# smarty01.net
KiCad netlist of a schematic drawn in EAGLE
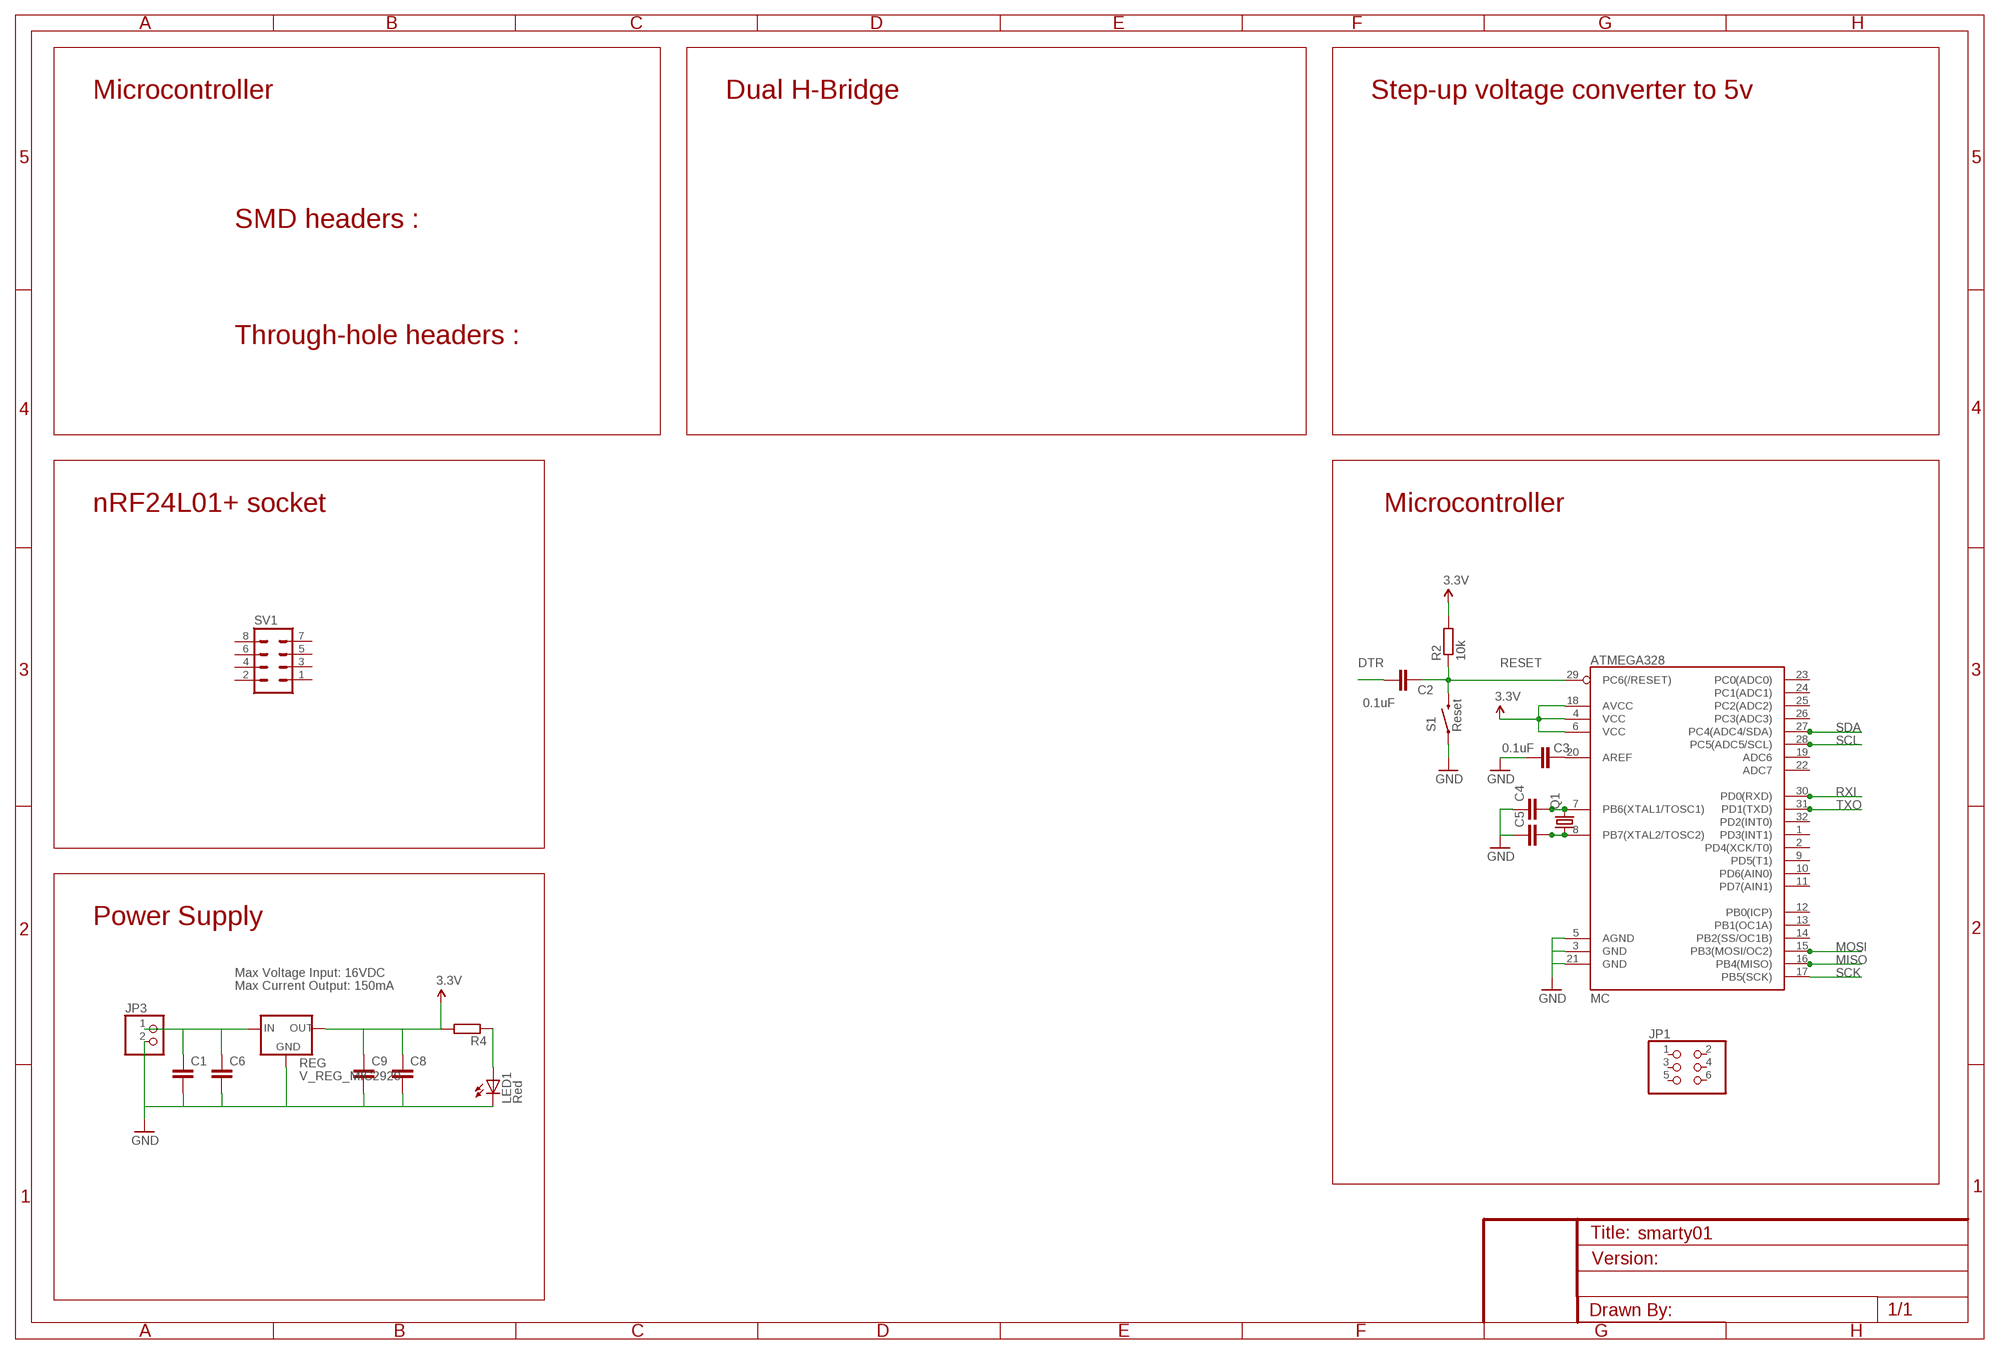
[diagram p0: schematic, sheet 1]

(export (version "E")
  (design (tool "Eeschema 10.0.6"))
  (components
    (comp (ref "C1")
      (value "C-EUC0805")
      (footprint "eagle-import:C0805")
      (libsource (lib "eagle-import") (part "C-EUC0805"))
    )
    (comp (ref "C2")
      (value "0.1uF")
      (footprint "eagle-import:C0805")
      (libsource (lib "eagle-import") (part "C-EUC0805"))
    )
    (comp (ref "C3")
      (value "0.1uF")
      (footprint "eagle-import:C0805")
      (libsource (lib "eagle-import") (part "C-EUC0805"))
    )
    (comp (ref "C4")
      (value "C-EUC0805")
      (footprint "eagle-import:C0805")
      (libsource (lib "eagle-import") (part "C-EUC0805"))
    )
    (comp (ref "C5")
      (value "C-EUC0805")
      (footprint "eagle-import:C0805")
      (libsource (lib "eagle-import") (part "C-EUC0805"))
    )
    (comp (ref "C6")
      (value "C-EUC0805")
      (footprint "eagle-import:C0805")
      (libsource (lib "eagle-import") (part "C-EUC0805"))
    )
    (comp (ref "C8")
      (value "C-EUC0805")
      (footprint "eagle-import:C0805")
      (libsource (lib "eagle-import") (part "C-EUC0805"))
    )
    (comp (ref "C9")
      (value "C-EUC0805")
      (footprint "eagle-import:C0805")
      (libsource (lib "eagle-import") (part "C-EUC0805"))
    )
    (comp (ref "JP1")
      (value "PINHD-2X03_2.54-SMD")
      (footprint "eagle-import:2X03SMD")
      (libsource (lib "eagle-import") (part "PINHD-2X03_2.54-SMD"))
    )
    (comp (ref "JP3")
      (value "PINHD-1X2")
      (footprint "eagle-import:1X02")
      (libsource (lib "eagle-import") (part "PINHD-1X2"))
    )
    (comp (ref "LED1")
      (value "Red")
      (footprint "eagle-import:LED-0603")
      (libsource (lib "eagle-import") (part "LED0603"))
    )
    (comp (ref "MC")
      (value "ATMEGA328")
      (footprint "eagle-import:TQFP32-08")
      (libsource (lib "eagle-import") (part "ATMEGA168"))
    )
    (comp (ref "Q1")
      (value "CRYSTALHC49UP")
      (footprint "eagle-import:HC49UP")
      (libsource (lib "eagle-import") (part "CRYSTALHC49UP"))
    )
    (comp (ref "R2")
      (value "10k")
      (footprint "eagle-import:R0805")
      (libsource (lib "eagle-import") (part "R-EU_R0805"))
    )
    (comp (ref "R4")
      (value "R-EU_R0805")
      (footprint "eagle-import:R0805")
      (libsource (lib "eagle-import") (part "R-EU_R0805"))
    )
    (comp (ref "REG")
      (value "V_REG_MIC2920")
      (footprint "eagle-import:SOT223")
      (libsource (lib "eagle-import") (part "V_REG_MIC2920"))
    )
    (comp (ref "S1")
      (value "Reset")
      (footprint "eagle-import:TACTILE_SWITCH_SMD")
      (libsource (lib "eagle-import") (part "SWITCH-MOMENTARY-2SMD"))
    )
    (comp (ref "SV1")
      (value "MA04-2")
      (footprint "eagle-import:MA04-2")
      (libsource (lib "eagle-import") (part "MA04-2"))
    )
  )
  (nets
    (net (code "1") (name "/DTR") (class "Default")
      (node (ref "C2") (pin "1") (pinfunction "1_1") (pintype "passive"))
    )
    (net (code "2") (name "/MISO") (class "Default")
      (node (ref "MC") (pin "16") (pinfunction "PB4(MISO)_16") (pintype "bidirectional"))
    )
    (net (code "3") (name "/MOSI") (class "Default")
      (node (ref "MC") (pin "15") (pinfunction "PB3(MOSI/OC2)_15") (pintype "bidirectional"))
    )
    (net (code "4") (name "/RESET") (class "Default")
      (node (ref "C2") (pin "2") (pinfunction "2_2") (pintype "passive"))
      (node (ref "MC") (pin "29") (pinfunction "PC6(/RESET)_29") (pintype "bidirectional"))
      (node (ref "R2") (pin "1") (pinfunction "1_1") (pintype "passive"))
      (node (ref "S1") (pin "3") (pinfunction "2_3") (pintype "passive"))
    )
    (net (code "5") (name "/RXI") (class "Default")
      (node (ref "MC") (pin "30") (pinfunction "PD0(RXD)_30") (pintype "bidirectional"))
    )
    (net (code "6") (name "/SCK") (class "Default")
      (node (ref "MC") (pin "17") (pinfunction "PB5(SCK)_17") (pintype "bidirectional"))
    )
    (net (code "7") (name "/SCL") (class "Default")
      (node (ref "MC") (pin "28") (pinfunction "PC5(ADC5/SCL)_28") (pintype "bidirectional"))
    )
    (net (code "8") (name "/SDA") (class "Default")
      (node (ref "MC") (pin "27") (pinfunction "PC4(ADC4/SDA)_27") (pintype "bidirectional"))
    )
    (net (code "9") (name "/TXO") (class "Default")
      (node (ref "MC") (pin "31") (pinfunction "PD1(TXD)_31") (pintype "bidirectional"))
    )
    (net (code "10") (name "3.3V") (class "Default")
      (node (ref "C8") (pin "1") (pinfunction "1_1") (pintype "passive"))
      (node (ref "C9") (pin "1") (pinfunction "1_1") (pintype "passive"))
      (node (ref "MC") (pin "18") (pinfunction "AVCC_18") (pintype "bidirectional"))
      (node (ref "MC") (pin "4") (pinfunction "VCC_4") (pintype "bidirectional"))
      (node (ref "MC") (pin "6") (pinfunction "VCC_6") (pintype "bidirectional"))
      (node (ref "R2") (pin "2") (pinfunction "2_2") (pintype "passive"))
      (node (ref "R4") (pin "2") (pinfunction "2_2") (pintype "passive"))
      (node (ref "REG") (pin "3") (pinfunction "OUT_3") (pintype "output"))
    )
    (net (code "11") (name "GND") (class "Default")
      (node (ref "C1") (pin "2") (pinfunction "2_2") (pintype "passive"))
      (node (ref "C3") (pin "2") (pinfunction "2_2") (pintype "passive"))
      (node (ref "C4") (pin "1") (pinfunction "1_1") (pintype "passive"))
      (node (ref "C5") (pin "1") (pinfunction "1_1") (pintype "passive"))
      (node (ref "C6") (pin "2") (pinfunction "2_2") (pintype "passive"))
      (node (ref "C8") (pin "2") (pinfunction "2_2") (pintype "passive"))
      (node (ref "C9") (pin "2") (pinfunction "2_2") (pintype "passive"))
      (node (ref "JP3") (pin "2") (pinfunction "2_2") (pintype "passive"))
      (node (ref "LED1") (pin "C") (pinfunction "C_C") (pintype "passive"))
      (node (ref "MC") (pin "21") (pinfunction "GND_21") (pintype "bidirectional"))
      (node (ref "MC") (pin "3") (pinfunction "GND_3") (pintype "bidirectional"))
      (node (ref "MC") (pin "5") (pinfunction "AGND_5") (pintype "bidirectional"))
      (node (ref "REG") (pin "2") (pinfunction "GND_2") (pintype "input"))
      (node (ref "S1") (pin "1") (pinfunction "1_1") (pintype "passive"))
    )
    (net (code "12") (name "Net-(LED1-PadA)") (class "Default")
      (node (ref "LED1") (pin "A") (pinfunction "A_A") (pintype "passive"))
      (node (ref "R4") (pin "1") (pinfunction "1_1") (pintype "passive"))
    )
    (net (code "13") (name "Net-(MC-AREF)") (class "Default")
      (node (ref "C3") (pin "1") (pinfunction "1_1") (pintype "passive"))
      (node (ref "MC") (pin "20") (pinfunction "AREF_20") (pintype "bidirectional"))
    )
    (net (code "14") (name "Net-(MC-PB6(XTAL1{slash}TOSC1))") (class "Default")
      (node (ref "C4") (pin "2") (pinfunction "2_2") (pintype "passive"))
      (node (ref "MC") (pin "7") (pinfunction "PB6(XTAL1/TOSC1)_7") (pintype "bidirectional"))
      (node (ref "Q1") (pin "2") (pinfunction "2_2") (pintype "passive"))
    )
    (net (code "15") (name "Net-(MC-PB7(XTAL2{slash}TOSC2))") (class "Default")
      (node (ref "C5") (pin "2") (pinfunction "2_2") (pintype "passive"))
      (node (ref "MC") (pin "8") (pinfunction "PB7(XTAL2/TOSC2)_8") (pintype "bidirectional"))
      (node (ref "Q1") (pin "1") (pinfunction "1_1") (pintype "passive"))
    )
    (net (code "16") (name "Net-(REG-IN)") (class "Default")
      (node (ref "C1") (pin "1") (pinfunction "1_1") (pintype "passive"))
      (node (ref "C6") (pin "1") (pinfunction "1_1") (pintype "passive"))
      (node (ref "JP3") (pin "1") (pinfunction "1_1") (pintype "passive"))
      (node (ref "REG") (pin "1") (pinfunction "IN_1") (pintype "input"))
    )
    (net (code "17") (name "unconnected-(JP1-Pad1)") (class "Default")
      (node (ref "JP1") (pin "1") (pinfunction "1_1") (pintype "passive"))
    )
    (net (code "18") (name "unconnected-(JP1-Pad2)") (class "Default")
      (node (ref "JP1") (pin "2") (pinfunction "2_2") (pintype "passive"))
    )
    (net (code "19") (name "unconnected-(JP1-Pad3)") (class "Default")
      (node (ref "JP1") (pin "3") (pinfunction "3_3") (pintype "passive"))
    )
    (net (code "20") (name "unconnected-(JP1-Pad4)") (class "Default")
      (node (ref "JP1") (pin "4") (pinfunction "4_4") (pintype "passive"))
    )
    (net (code "21") (name "unconnected-(JP1-Pad5)") (class "Default")
      (node (ref "JP1") (pin "5") (pinfunction "5_5") (pintype "passive"))
    )
    (net (code "22") (name "unconnected-(JP1-Pad6)") (class "Default")
      (node (ref "JP1") (pin "6") (pinfunction "6_6") (pintype "passive"))
    )
    (net (code "23") (name "unconnected-(MC-ADC6-Pad19)") (class "Default")
      (node (ref "MC") (pin "19") (pinfunction "ADC6_19") (pintype "bidirectional"))
    )
    (net (code "24") (name "unconnected-(MC-ADC7-Pad22)") (class "Default")
      (node (ref "MC") (pin "22") (pinfunction "ADC7_22") (pintype "bidirectional"))
    )
    (net (code "25") (name "unconnected-(MC-PB0(ICP)-Pad12)") (class "Default")
      (node (ref "MC") (pin "12") (pinfunction "PB0(ICP)_12") (pintype "bidirectional"))
    )
    (net (code "26") (name "unconnected-(MC-PB1(OC1A)-Pad13)") (class "Default")
      (node (ref "MC") (pin "13") (pinfunction "PB1(OC1A)_13") (pintype "bidirectional"))
    )
    (net (code "27") (name "unconnected-(MC-PB2(SS{slash}OC1B)-Pad14)") (class "Default")
      (node (ref "MC") (pin "14") (pinfunction "PB2(SS/OC1B)_14") (pintype "bidirectional"))
    )
    (net (code "28") (name "unconnected-(MC-PC0(ADC0)-Pad23)") (class "Default")
      (node (ref "MC") (pin "23") (pinfunction "PC0(ADC0)_23") (pintype "bidirectional"))
    )
    (net (code "29") (name "unconnected-(MC-PC1(ADC1)-Pad24)") (class "Default")
      (node (ref "MC") (pin "24") (pinfunction "PC1(ADC1)_24") (pintype "bidirectional"))
    )
    (net (code "30") (name "unconnected-(MC-PC2(ADC2)-Pad25)") (class "Default")
      (node (ref "MC") (pin "25") (pinfunction "PC2(ADC2)_25") (pintype "bidirectional"))
    )
    (net (code "31") (name "unconnected-(MC-PC3(ADC3)-Pad26)") (class "Default")
      (node (ref "MC") (pin "26") (pinfunction "PC3(ADC3)_26") (pintype "bidirectional"))
    )
    (net (code "32") (name "unconnected-(MC-PD2(INT0)-Pad32)") (class "Default")
      (node (ref "MC") (pin "32") (pinfunction "PD2(INT0)_32") (pintype "bidirectional"))
    )
    (net (code "33") (name "unconnected-(MC-PD3(INT1)-Pad1)") (class "Default")
      (node (ref "MC") (pin "1") (pinfunction "PD3(INT1)_1") (pintype "bidirectional"))
    )
    (net (code "34") (name "unconnected-(MC-PD4(XCK{slash}T0)-Pad2)") (class "Default")
      (node (ref "MC") (pin "2") (pinfunction "PD4(XCK/T0)_2") (pintype "bidirectional"))
    )
    (net (code "35") (name "unconnected-(MC-PD5(T1)-Pad9)") (class "Default")
      (node (ref "MC") (pin "9") (pinfunction "PD5(T1)_9") (pintype "bidirectional"))
    )
    (net (code "36") (name "unconnected-(MC-PD6(AIN0)-Pad10)") (class "Default")
      (node (ref "MC") (pin "10") (pinfunction "PD6(AIN0)_10") (pintype "bidirectional"))
    )
    (net (code "37") (name "unconnected-(MC-PD7(AIN1)-Pad11)") (class "Default")
      (node (ref "MC") (pin "11") (pinfunction "PD7(AIN1)_11") (pintype "bidirectional"))
    )
    (net (code "38") (name "unconnected-(SV1-Pad1)") (class "Default")
      (node (ref "SV1") (pin "1") (pinfunction "1_1") (pintype "passive"))
    )
    (net (code "39") (name "unconnected-(SV1-Pad2)") (class "Default")
      (node (ref "SV1") (pin "2") (pinfunction "2_2") (pintype "passive"))
    )
    (net (code "40") (name "unconnected-(SV1-Pad3)") (class "Default")
      (node (ref "SV1") (pin "3") (pinfunction "3_3") (pintype "passive"))
    )
    (net (code "41") (name "unconnected-(SV1-Pad4)") (class "Default")
      (node (ref "SV1") (pin "4") (pinfunction "4_4") (pintype "passive"))
    )
    (net (code "42") (name "unconnected-(SV1-Pad5)") (class "Default")
      (node (ref "SV1") (pin "5") (pinfunction "5_5") (pintype "passive"))
    )
    (net (code "43") (name "unconnected-(SV1-Pad6)") (class "Default")
      (node (ref "SV1") (pin "6") (pinfunction "6_6") (pintype "passive"))
    )
    (net (code "44") (name "unconnected-(SV1-Pad7)") (class "Default")
      (node (ref "SV1") (pin "7") (pinfunction "7_7") (pintype "passive"))
    )
    (net (code "45") (name "unconnected-(SV1-Pad8)") (class "Default")
      (node (ref "SV1") (pin "8") (pinfunction "8_8") (pintype "passive"))
    )
  )
)
